# SPI_LVDS.net
KiCad netlist of a schematic drawn in Altium Designer
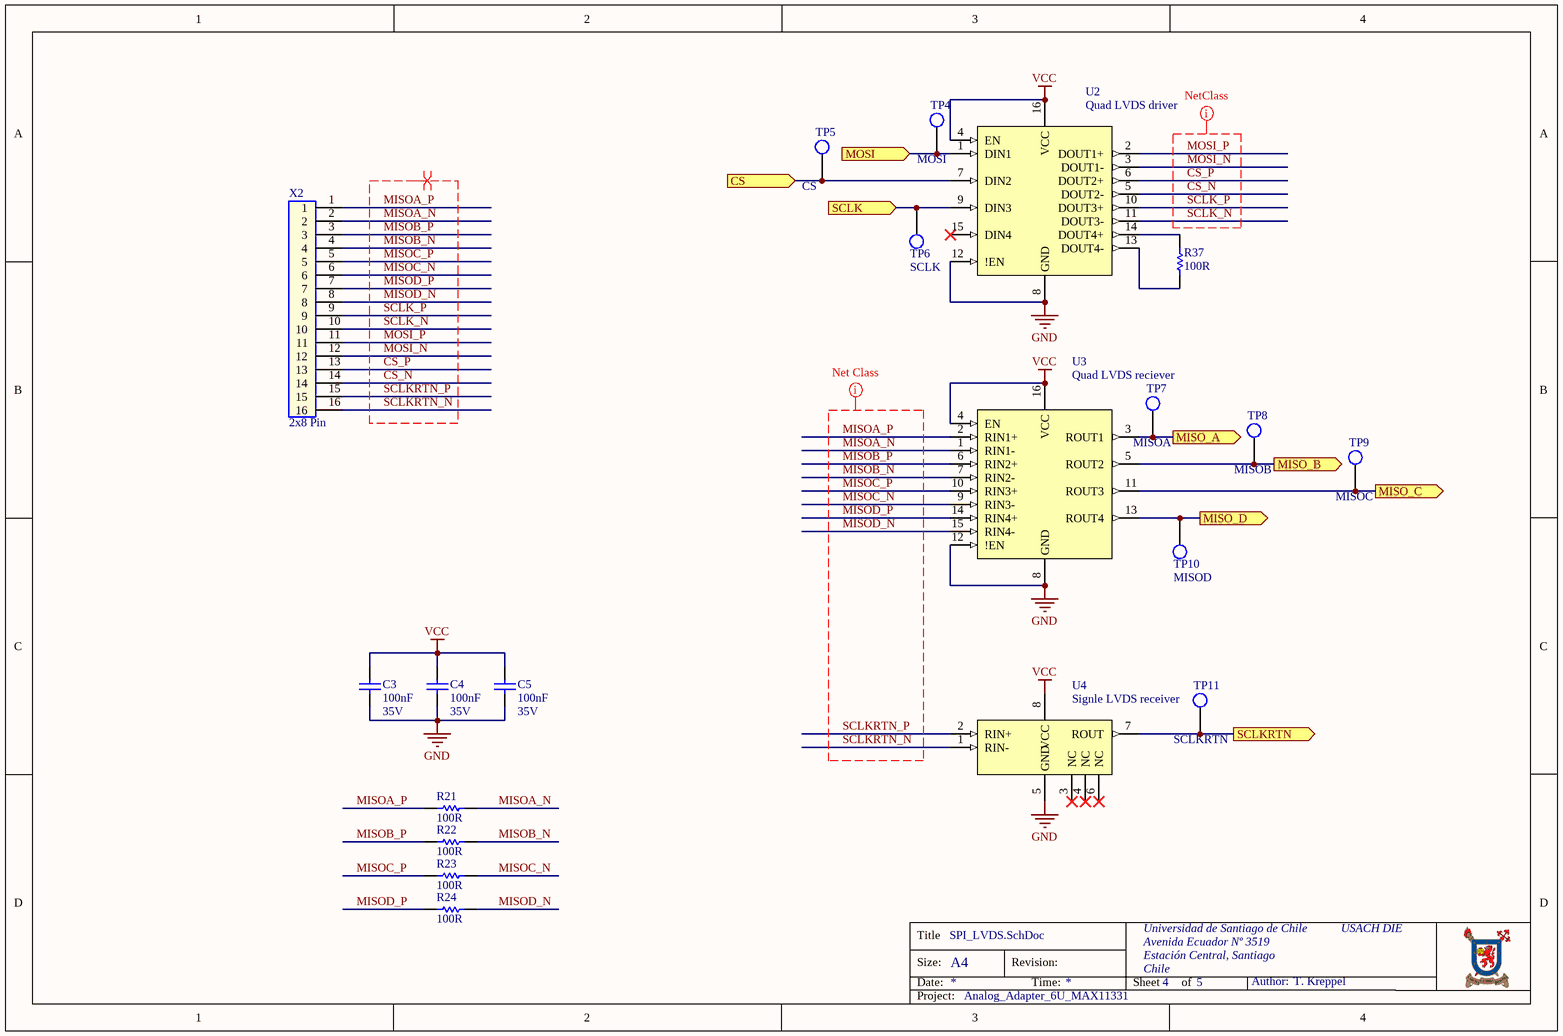
[diagram p0: SPI_LVDS.SchDoc]

(export (version "E")
  (design (tool "Eeschema 10.0.6"))
  (components
    (comp (ref "C3")
      (value "100nF")
      (footprint "CAP_0603")
      (description "Capacitor")
      (fields
        (field (name "MPN") "C0603C104M5RACTU")
        (field (name "MF") "KEMET")
        (field (name "VOLTAGE") "35V")
        (field (name "PUBLISHER") "Altium Limited")
      )
      (libsource (lib "Componentes_SOC") (part "Cap_0603"))
    )
    (comp (ref "C4")
      (value "100nF")
      (footprint "CAP_0603")
      (description "Capacitor")
      (fields
        (field (name "MPN") "C0603C104M5RACTU")
        (field (name "MF") "KEMET")
        (field (name "VOLTAGE") "35V")
        (field (name "PUBLISHER") "Altium Limited")
      )
      (libsource (lib "Componentes_SOC") (part "Cap_0603"))
    )
    (comp (ref "C5")
      (value "100nF")
      (footprint "CAP_0603")
      (description "Capacitor")
      (fields
        (field (name "MPN") "C0603C104M5RACTU")
        (field (name "MF") "KEMET")
        (field (name "VOLTAGE") "35V")
        (field (name "PUBLISHER") "Altium Limited")
      )
      (libsource (lib "Componentes_SOC") (part "Cap_0603"))
    )
    (comp (ref "R21")
      (value "100R")
      (footprint "RES_0603")
      (fields
        (field (name "TOLERANCE") "1%")
        (field (name "LCSC PART NUMBER") "C22775")
        (field (name "PUBLISHER") "Altium Limited")
      )
      (libsource (lib "Componentes_SOC") (part "Res0603"))
    )
    (comp (ref "R22")
      (value "100R")
      (footprint "RES_0603")
      (fields
        (field (name "TOLERANCE") "1%")
        (field (name "LCSC PART NUMBER") "C22775")
        (field (name "PUBLISHER") "Altium Limited")
      )
      (libsource (lib "Componentes_SOC") (part "Res0603"))
    )
    (comp (ref "R23")
      (value "100R")
      (footprint "RES_0603")
      (fields
        (field (name "TOLERANCE") "1%")
        (field (name "LCSC PART NUMBER") "C22775")
        (field (name "PUBLISHER") "Altium Limited")
      )
      (libsource (lib "Componentes_SOC") (part "Res0603"))
    )
    (comp (ref "R24")
      (value "100R")
      (footprint "RES_0603")
      (fields
        (field (name "TOLERANCE") "1%")
        (field (name "LCSC PART NUMBER") "C22775")
        (field (name "PUBLISHER") "Altium Limited")
      )
      (libsource (lib "Componentes_SOC") (part "Res0603"))
    )
    (comp (ref "R37")
      (value "100R")
      (footprint "RES_0603")
      (fields
        (field (name "TOLERANCE") "1%")
        (field (name "LCSC PART NUMBER") "C22775")
        (field (name "PUBLISHER") "Altium Limited")
      )
      (libsource (lib "Componentes_SOC") (part "Res0603"))
    )
    (comp (ref "TP4")
      (value "MOSI")
      (footprint "TP_1.6mm")
      (description "1.6mm Test Point Keystone")
      (fields
        (field (name "MF") "Keystone Electronics")
        (field (name "MPN") "5006")
        (field (name "CREATED") "2020_04_Kreppel")
      )
      (libsource (lib "Componentes_SOC") (part "TP"))
    )
    (comp (ref "TP5")
      (value "CS")
      (footprint "TP_1.6mm")
      (description "1.6mm Test Point Keystone")
      (fields
        (field (name "MF") "Keystone Electronics")
        (field (name "MPN") "5006")
        (field (name "CREATED") "2020_04_Kreppel")
      )
      (libsource (lib "Componentes_SOC") (part "TP"))
    )
    (comp (ref "TP6")
      (value "SCLK")
      (footprint "TP_1.6mm")
      (description "1.6mm Test Point Keystone")
      (fields
        (field (name "MF") "Keystone Electronics")
        (field (name "MPN") "5006")
        (field (name "CREATED") "2020_04_Kreppel")
      )
      (libsource (lib "Componentes_SOC") (part "TP"))
    )
    (comp (ref "TP7")
      (value "MISOA")
      (footprint "TP_1.6mm")
      (description "1.6mm Test Point Keystone")
      (fields
        (field (name "MF") "Keystone Electronics")
        (field (name "MPN") "5006")
        (field (name "CREATED") "2020_04_Kreppel")
      )
      (libsource (lib "Componentes_SOC") (part "TP"))
    )
    (comp (ref "TP8")
      (value "MISOB")
      (footprint "TP_1.6mm")
      (description "1.6mm Test Point Keystone")
      (fields
        (field (name "MF") "Keystone Electronics")
        (field (name "MPN") "5006")
        (field (name "CREATED") "2020_04_Kreppel")
      )
      (libsource (lib "Componentes_SOC") (part "TP"))
    )
    (comp (ref "TP9")
      (value "MISOC")
      (footprint "TP_1.6mm")
      (description "1.6mm Test Point Keystone")
      (fields
        (field (name "MF") "Keystone Electronics")
        (field (name "MPN") "5006")
        (field (name "CREATED") "2020_04_Kreppel")
      )
      (libsource (lib "Componentes_SOC") (part "TP"))
    )
    (comp (ref "TP10")
      (value "MISOD")
      (footprint "TP_1.6mm")
      (description "1.6mm Test Point Keystone")
      (fields
        (field (name "MF") "Keystone Electronics")
        (field (name "MPN") "5006")
        (field (name "CREATED") "2020_04_Kreppel")
      )
      (libsource (lib "Componentes_SOC") (part "TP"))
    )
    (comp (ref "TP11")
      (value "SCLKRTN")
      (footprint "TP_1.6mm")
      (description "1.6mm Test Point Keystone")
      (fields
        (field (name "MF") "Keystone Electronics")
        (field (name "MPN") "5006")
        (field (name "CREATED") "2020_04_Kreppel")
      )
      (libsource (lib "Componentes_SOC") (part "TP"))
    )
    (comp (ref "U2")
      (value "Quad LVDS driver")
      (footprint "TSOP65P640X120-16N")
      (description "3V, LVDS, Quad, CMOS Differential Line Driver")
      (fields
        (field (name "MF") "Analog Devices")
        (field (name "MPN") "ADN4665ARUZ")
        (field (name "CREATED") "2020_05_Kreppel")
      )
      (libsource (lib "Componentes_SOC") (part "ADN4665"))
    )
    (comp (ref "U3")
      (value "Quad LVDS reciever")
      (footprint "TSOP65P640X120-16N")
      (description "3V, LVDS, quad, CMOS Differential Line Receiver")
      (fields
        (field (name "MF") "Analog Devices")
        (field (name "MPN") "ADN4666ARUZ")
        (field (name "CREATED") "2020_05_Kreppel")
      )
      (libsource (lib "Componentes_SOC") (part "ADN4666"))
    )
    (comp (ref "U4")
      (value "Signle LVDS receiver")
      (footprint "SOIC127P600X170_HS-9N_no_THP")
      (description "Single, 3V, CMOS, LVDS High Speed Differential Receiver")
      (fields
        (field (name "MF") "Analog Devices")
        (field (name "MPN") "ADN4662BRZ")
        (field (name "CREATED") "2020_05_Kreppel")
      )
      (libsource (lib "Componentes_SOC") (part "ADN4662"))
    )
    (comp (ref "X2")
      (value "2x8 Pin")
      (footprint "EHF-108-01-F-D")
      (description "Dual Row, 2x8 Shrouded IDC Header with Ejectors 50 mil pitch")
      (fields
        (field (name "MF") "Samtec")
        (field (name "MPN") "EHF-108-01-F-D")
        (field (name "CREATED") "2020_05_Kreppel")
      )
      (libsource (lib "Componentes_SOC") (part "EHF-108-01-F-D"))
    )
  )
  (nets
    (net (code "1") (name "/CS") (class "Default")
      (node (ref "TP5") (pin "1") (pinfunction "1_1") (pintype "passive"))
      (node (ref "U2") (pin "7") (pinfunction "DIN2_7") (pintype "input"))
    )
    (net (code "2") (name "/CS_N") (class "Default")
      (node (ref "U2") (pin "5") (pinfunction "DOUT2-_5") (pintype "output"))
      (node (ref "X2") (pin "14") (pinfunction "14_14") (pintype "passive"))
    )
    (net (code "3") (name "/CS_P") (class "Default")
      (node (ref "U2") (pin "6") (pinfunction "DOUT2+_6") (pintype "output"))
      (node (ref "X2") (pin "13") (pinfunction "13_13") (pintype "passive"))
    )
    (net (code "4") (name "/MISOA_N") (class "Default")
      (node (ref "R21") (pin "1") (pinfunction "1_1") (pintype "passive"))
      (node (ref "U3") (pin "1") (pinfunction "RIN1-_1") (pintype "input"))
      (node (ref "X2") (pin "2") (pinfunction "2_2") (pintype "passive"))
    )
    (net (code "5") (name "/MISOA_P") (class "Default")
      (node (ref "R21") (pin "2") (pinfunction "2_2") (pintype "passive"))
      (node (ref "U3") (pin "2") (pinfunction "RIN1+_2") (pintype "input"))
      (node (ref "X2") (pin "1") (pinfunction "1_1") (pintype "passive"))
    )
    (net (code "6") (name "/MISOB_N") (class "Default")
      (node (ref "R22") (pin "1") (pinfunction "1_1") (pintype "passive"))
      (node (ref "U3") (pin "7") (pinfunction "RIN2-_7") (pintype "input"))
      (node (ref "X2") (pin "4") (pinfunction "4_4") (pintype "passive"))
    )
    (net (code "7") (name "/MISOB_P") (class "Default")
      (node (ref "R22") (pin "2") (pinfunction "2_2") (pintype "passive"))
      (node (ref "U3") (pin "6") (pinfunction "RIN2+_6") (pintype "input"))
      (node (ref "X2") (pin "3") (pinfunction "3_3") (pintype "passive"))
    )
    (net (code "8") (name "/MISOC_N") (class "Default")
      (node (ref "R23") (pin "1") (pinfunction "1_1") (pintype "passive"))
      (node (ref "U3") (pin "9") (pinfunction "RIN3-_9") (pintype "input"))
      (node (ref "X2") (pin "6") (pinfunction "6_6") (pintype "passive"))
    )
    (net (code "9") (name "/MISOC_P") (class "Default")
      (node (ref "R23") (pin "2") (pinfunction "2_2") (pintype "passive"))
      (node (ref "U3") (pin "10") (pinfunction "RIN3+_10") (pintype "input"))
      (node (ref "X2") (pin "5") (pinfunction "5_5") (pintype "passive"))
    )
    (net (code "10") (name "/MISOD_N") (class "Default")
      (node (ref "R24") (pin "1") (pinfunction "1_1") (pintype "passive"))
      (node (ref "U3") (pin "15") (pinfunction "RIN4-_15") (pintype "input"))
      (node (ref "X2") (pin "8") (pinfunction "8_8") (pintype "passive"))
    )
    (net (code "11") (name "/MISOD_P") (class "Default")
      (node (ref "R24") (pin "2") (pinfunction "2_2") (pintype "passive"))
      (node (ref "U3") (pin "14") (pinfunction "RIN4+_14") (pintype "input"))
      (node (ref "X2") (pin "7") (pinfunction "7_7") (pintype "passive"))
    )
    (net (code "12") (name "/MISO_A") (class "Default")
      (node (ref "TP7") (pin "1") (pinfunction "1_1") (pintype "passive"))
      (node (ref "U3") (pin "3") (pinfunction "ROUT1_3") (pintype "output"))
    )
    (net (code "13") (name "/MISO_B") (class "Default")
      (node (ref "TP8") (pin "1") (pinfunction "1_1") (pintype "passive"))
      (node (ref "U3") (pin "5") (pinfunction "ROUT2_5") (pintype "output"))
    )
    (net (code "14") (name "/MISO_C") (class "Default")
      (node (ref "TP9") (pin "1") (pinfunction "1_1") (pintype "passive"))
      (node (ref "U3") (pin "11") (pinfunction "ROUT3_11") (pintype "output"))
    )
    (net (code "15") (name "/MISO_D") (class "Default")
      (node (ref "TP10") (pin "1") (pinfunction "1_1") (pintype "passive"))
      (node (ref "U3") (pin "13") (pinfunction "ROUT4_13") (pintype "output"))
    )
    (net (code "16") (name "/MOSI") (class "Default")
      (node (ref "TP4") (pin "1") (pinfunction "1_1") (pintype "passive"))
      (node (ref "U2") (pin "1") (pinfunction "DIN1_1") (pintype "input"))
    )
    (net (code "17") (name "/MOSI_N") (class "Default")
      (node (ref "U2") (pin "3") (pinfunction "DOUT1-_3") (pintype "output"))
      (node (ref "X2") (pin "12") (pinfunction "12_12") (pintype "passive"))
    )
    (net (code "18") (name "/MOSI_P") (class "Default")
      (node (ref "U2") (pin "2") (pinfunction "DOUT1+_2") (pintype "output"))
      (node (ref "X2") (pin "11") (pinfunction "11_11") (pintype "passive"))
    )
    (net (code "19") (name "/SCLK") (class "Default")
      (node (ref "TP6") (pin "1") (pinfunction "1_1") (pintype "passive"))
      (node (ref "U2") (pin "9") (pinfunction "DIN3_9") (pintype "input"))
    )
    (net (code "20") (name "/SCLKRTN") (class "Default")
      (node (ref "TP11") (pin "1") (pinfunction "1_1") (pintype "passive"))
      (node (ref "U4") (pin "7") (pinfunction "ROUT_7") (pintype "output"))
    )
    (net (code "21") (name "/SCLKRTN_N") (class "Default")
      (node (ref "U4") (pin "1") (pinfunction "RIN-_1") (pintype "input"))
      (node (ref "X2") (pin "16") (pinfunction "16_16") (pintype "passive"))
    )
    (net (code "22") (name "/SCLKRTN_P") (class "Default")
      (node (ref "U4") (pin "2") (pinfunction "RIN+_2") (pintype "input"))
      (node (ref "X2") (pin "15") (pinfunction "15_15") (pintype "passive"))
    )
    (net (code "23") (name "/SCLK_N") (class "Default")
      (node (ref "U2") (pin "11") (pinfunction "DOUT3-_11") (pintype "output"))
      (node (ref "X2") (pin "10") (pinfunction "10_10") (pintype "passive"))
    )
    (net (code "24") (name "/SCLK_P") (class "Default")
      (node (ref "U2") (pin "10") (pinfunction "DOUT3+_10") (pintype "output"))
      (node (ref "X2") (pin "9") (pinfunction "9_9") (pintype "passive"))
    )
    (net (code "25") (name "GND") (class "Default")
      (node (ref "C3") (pin "2") (pinfunction "2_2") (pintype "passive"))
      (node (ref "C4") (pin "2") (pinfunction "2_2") (pintype "passive"))
      (node (ref "C5") (pin "2") (pinfunction "2_2") (pintype "passive"))
      (node (ref "U2") (pin "12") (pinfunction "!EN_12") (pintype "input"))
      (node (ref "U2") (pin "8") (pinfunction "GND_8") (pintype "power_in"))
      (node (ref "U3") (pin "12") (pinfunction "!EN_12") (pintype "input"))
      (node (ref "U3") (pin "8") (pinfunction "GND_8") (pintype "power_in"))
      (node (ref "U4") (pin "5") (pinfunction "GND_5") (pintype "power_in"))
    )
    (net (code "26") (name "Net-(U2-DOUT4+)") (class "Default")
      (node (ref "R37") (pin "1") (pinfunction "1_1") (pintype "passive"))
      (node (ref "U2") (pin "14") (pinfunction "DOUT4+_14") (pintype "output"))
    )
    (net (code "27") (name "Net-(U2-DOUT4-)") (class "Default")
      (node (ref "R37") (pin "2") (pinfunction "2_2") (pintype "passive"))
      (node (ref "U2") (pin "13") (pinfunction "DOUT4-_13") (pintype "output"))
    )
    (net (code "28") (name "VCC") (class "Default")
      (node (ref "C3") (pin "1") (pinfunction "1_1") (pintype "passive"))
      (node (ref "C4") (pin "1") (pinfunction "1_1") (pintype "passive"))
      (node (ref "C5") (pin "1") (pinfunction "1_1") (pintype "passive"))
      (node (ref "U2") (pin "16") (pinfunction "VCC_16") (pintype "power_in"))
      (node (ref "U2") (pin "4") (pinfunction "EN_4") (pintype "input"))
      (node (ref "U3") (pin "16") (pinfunction "VCC_16") (pintype "power_in"))
      (node (ref "U3") (pin "4") (pinfunction "EN_4") (pintype "input"))
      (node (ref "U4") (pin "8") (pinfunction "VCC_8") (pintype "power_in"))
    )
    (net (code "29") (name "unconnected-(U2-DIN4-Pad15)") (class "Default")
      (node (ref "U2") (pin "15") (pinfunction "DIN4_15") (pintype "input+no_connect"))
    )
    (net (code "30") (name "unconnected-(U4-NC-Pad3)") (class "Default")
      (node (ref "U4") (pin "3") (pinfunction "NC_3") (pintype "passive+no_connect"))
    )
    (net (code "31") (name "unconnected-(U4-NC-Pad4)") (class "Default")
      (node (ref "U4") (pin "4") (pinfunction "NC_4") (pintype "passive+no_connect"))
    )
    (net (code "32") (name "unconnected-(U4-NC-Pad6)") (class "Default")
      (node (ref "U4") (pin "6") (pinfunction "NC_6") (pintype "passive+no_connect"))
    )
  )
)
